# working.net
KiCad netlist of a schematic drawn in EAGLE
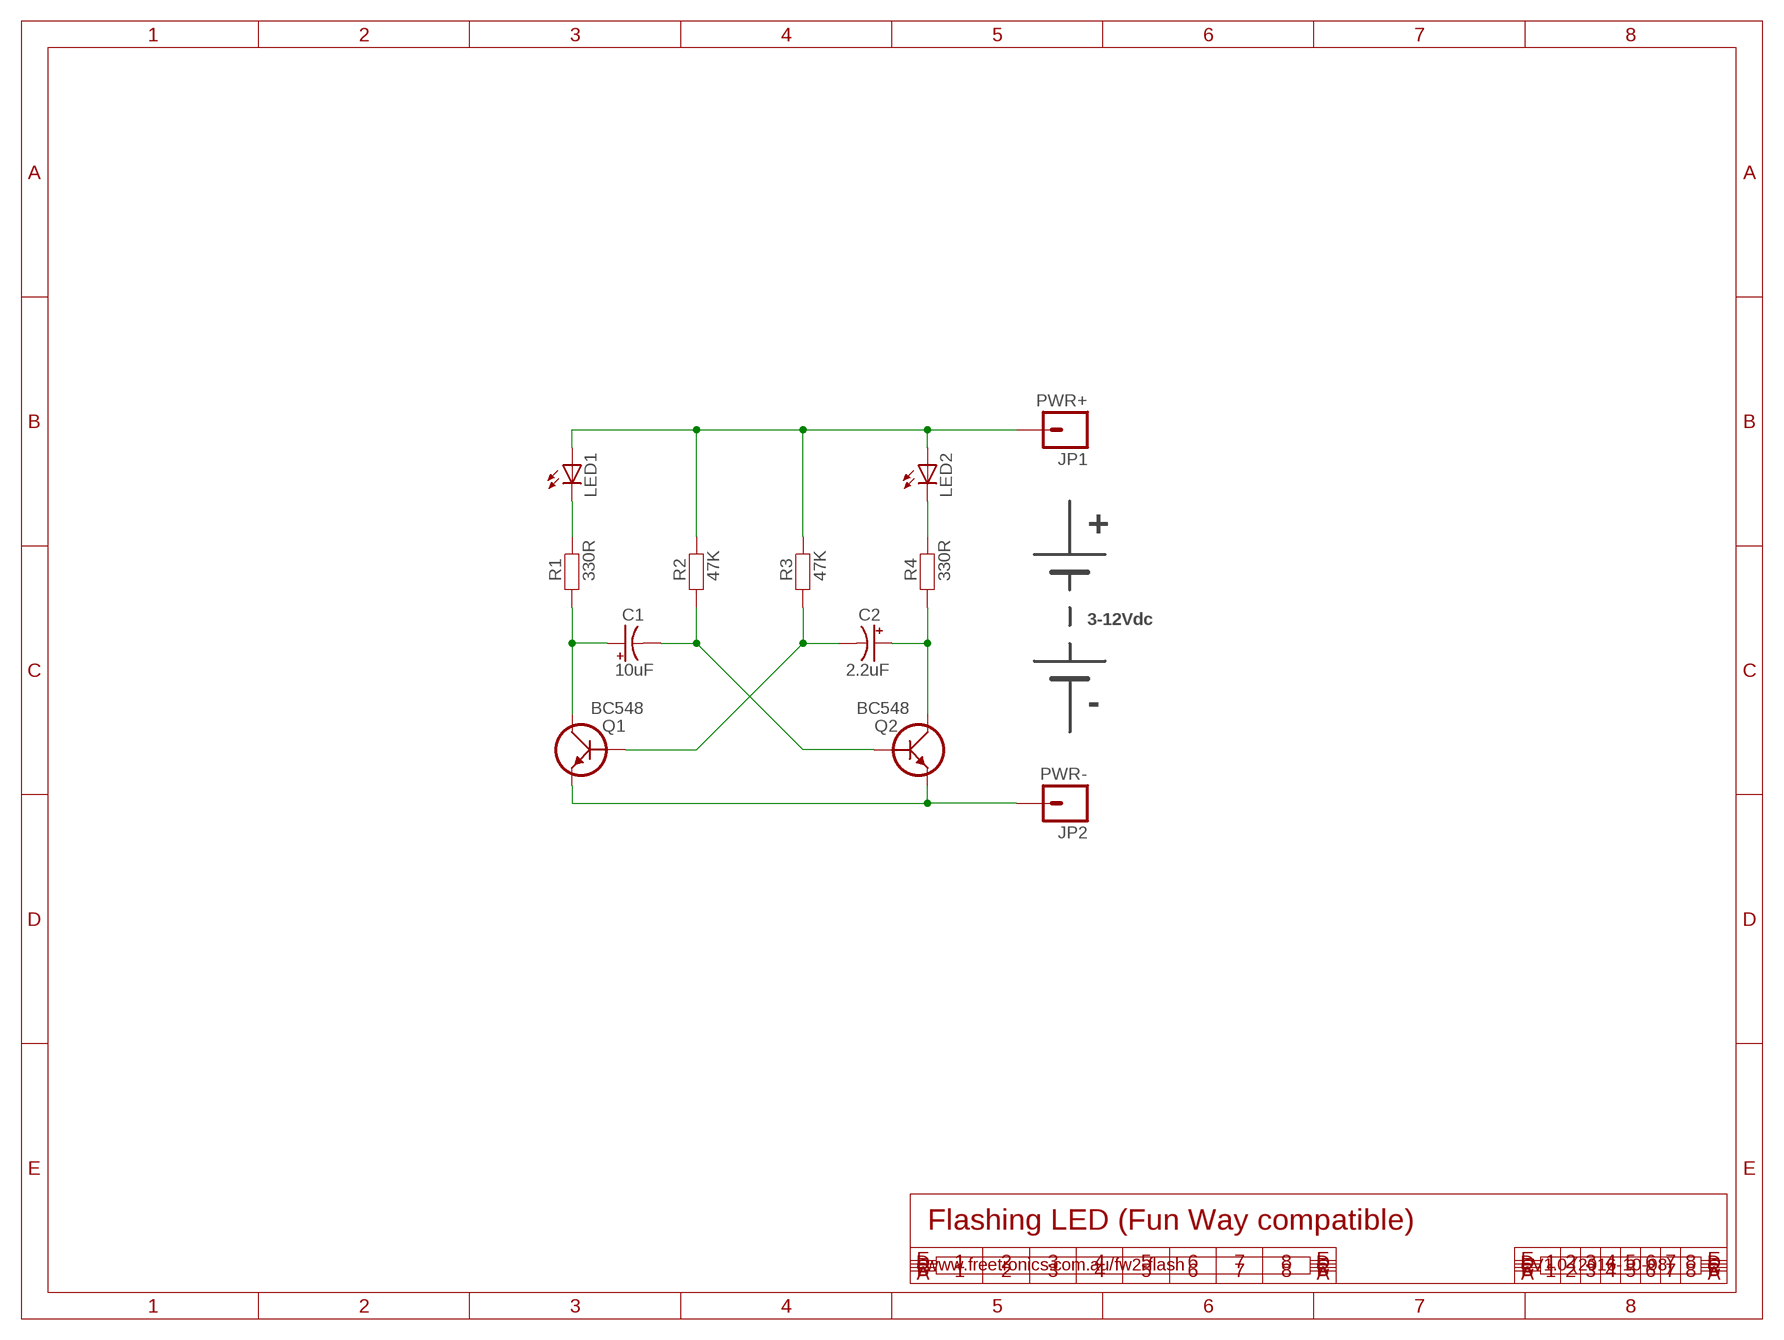
[diagram p0: schematic, sheet 1]

(export (version "E")
  (design (tool "Eeschema 10.0.6"))
  (components
    (comp (ref "C1")
      (value "10uF")
      (footprint "eagle-import:E5-5")
      (libsource (lib "eagle-import") (part "CPOL-USE5-5"))
    )
    (comp (ref "C2")
      (value "2.2uF")
      (footprint "eagle-import:E5-5")
      (libsource (lib "eagle-import") (part "CPOL-USE5-5"))
    )
    (comp (ref "JP1")
      (value "PWR+")
      (footprint "eagle-import:1X01")
      (libsource (lib "eagle-import") (part "M01PTH"))
    )
    (comp (ref "JP2")
      (value "PWR-")
      (footprint "eagle-import:1X01")
      (libsource (lib "eagle-import") (part "M01PTH"))
    )
    (comp (ref "LED1")
      (value "LED5MML")
      (footprint "eagle-import:LED5MMLARGE")
      (libsource (lib "eagle-import") (part "LED5MML"))
    )
    (comp (ref "LED2")
      (value "LED5MML")
      (footprint "eagle-import:LED5MMLARGE")
      (libsource (lib "eagle-import") (part "LED5MML"))
    )
    (comp (ref "Q1")
      (value "BC548")
      (footprint "eagle-import:TO-92")
      (libsource (lib "eagle-import") (part "BC547"))
    )
    (comp (ref "Q2")
      (value "BC548")
      (footprint "eagle-import:TO-92")
      (libsource (lib "eagle-import") (part "BC547"))
    )
    (comp (ref "R1")
      (value "330R")
      (footprint "eagle-import:AXIAL-0.4-LARGE")
      (libsource (lib "eagle-import") (part "FREETRONICS_RESISTORPTH3"))
    )
    (comp (ref "R2")
      (value "47K")
      (footprint "eagle-import:AXIAL-0.4-LARGE")
      (libsource (lib "eagle-import") (part "FREETRONICS_RESISTORPTH3"))
    )
    (comp (ref "R3")
      (value "47K")
      (footprint "eagle-import:AXIAL-0.4-LARGE")
      (libsource (lib "eagle-import") (part "FREETRONICS_RESISTORPTH3"))
    )
    (comp (ref "R4")
      (value "330R")
      (footprint "eagle-import:AXIAL-0.4-LARGE")
      (libsource (lib "eagle-import") (part "FREETRONICS_RESISTORPTH3"))
    )
  )
  (nets
    (net (code "1") (name "Net-(LED1-C)") (class "Default")
      (node (ref "LED1") (pin "K") (pinfunction "C_K") (pintype "passive"))
      (node (ref "R1") (pin "P$2") (pinfunction "2_P$2") (pintype "passive"))
    )
    (net (code "2") (name "Net-(LED2-C)") (class "Default")
      (node (ref "LED2") (pin "K") (pinfunction "C_K") (pintype "passive"))
      (node (ref "R4") (pin "P$2") (pinfunction "2_P$2") (pintype "passive"))
    )
    (net (code "3") (name "Net-(Q1-B)") (class "Default")
      (node (ref "C2") (pin "-") (pinfunction "-_-") (pintype "passive"))
      (node (ref "Q1") (pin "2") (pinfunction "B_2") (pintype "passive"))
      (node (ref "R3") (pin "P$1") (pinfunction "1_P$1") (pintype "passive"))
    )
    (net (code "4") (name "Net-(Q1-C)") (class "Default")
      (node (ref "C1") (pin "+") (pinfunction "+_+") (pintype "passive"))
      (node (ref "Q1") (pin "1") (pinfunction "C_1") (pintype "passive"))
      (node (ref "R1") (pin "P$1") (pinfunction "1_P$1") (pintype "passive"))
    )
    (net (code "5") (name "Net-(Q1-E)") (class "Default")
      (node (ref "JP2") (pin "1") (pinfunction "1_1") (pintype "passive"))
      (node (ref "Q1") (pin "3") (pinfunction "E_3") (pintype "passive"))
      (node (ref "Q2") (pin "3") (pinfunction "E_3") (pintype "passive"))
    )
    (net (code "6") (name "Net-(Q2-B)") (class "Default")
      (node (ref "C1") (pin "-") (pinfunction "-_-") (pintype "passive"))
      (node (ref "Q2") (pin "2") (pinfunction "B_2") (pintype "passive"))
      (node (ref "R2") (pin "P$1") (pinfunction "1_P$1") (pintype "passive"))
    )
    (net (code "7") (name "Net-(Q2-C)") (class "Default")
      (node (ref "C2") (pin "+") (pinfunction "+_+") (pintype "passive"))
      (node (ref "Q2") (pin "1") (pinfunction "C_1") (pintype "passive"))
      (node (ref "R4") (pin "P$1") (pinfunction "1_P$1") (pintype "passive"))
    )
    (net (code "8") (name "Net-(R2-2)") (class "Default")
      (node (ref "JP1") (pin "1") (pinfunction "1_1") (pintype "passive"))
      (node (ref "LED1") (pin "A") (pinfunction "A_A") (pintype "passive"))
      (node (ref "LED2") (pin "A") (pinfunction "A_A") (pintype "passive"))
      (node (ref "R2") (pin "P$2") (pinfunction "2_P$2") (pintype "passive"))
      (node (ref "R3") (pin "P$2") (pinfunction "2_P$2") (pintype "passive"))
    )
  )
)
